# EtherWiz.net
KiCad netlist of a schematic drawn in Altium Designer
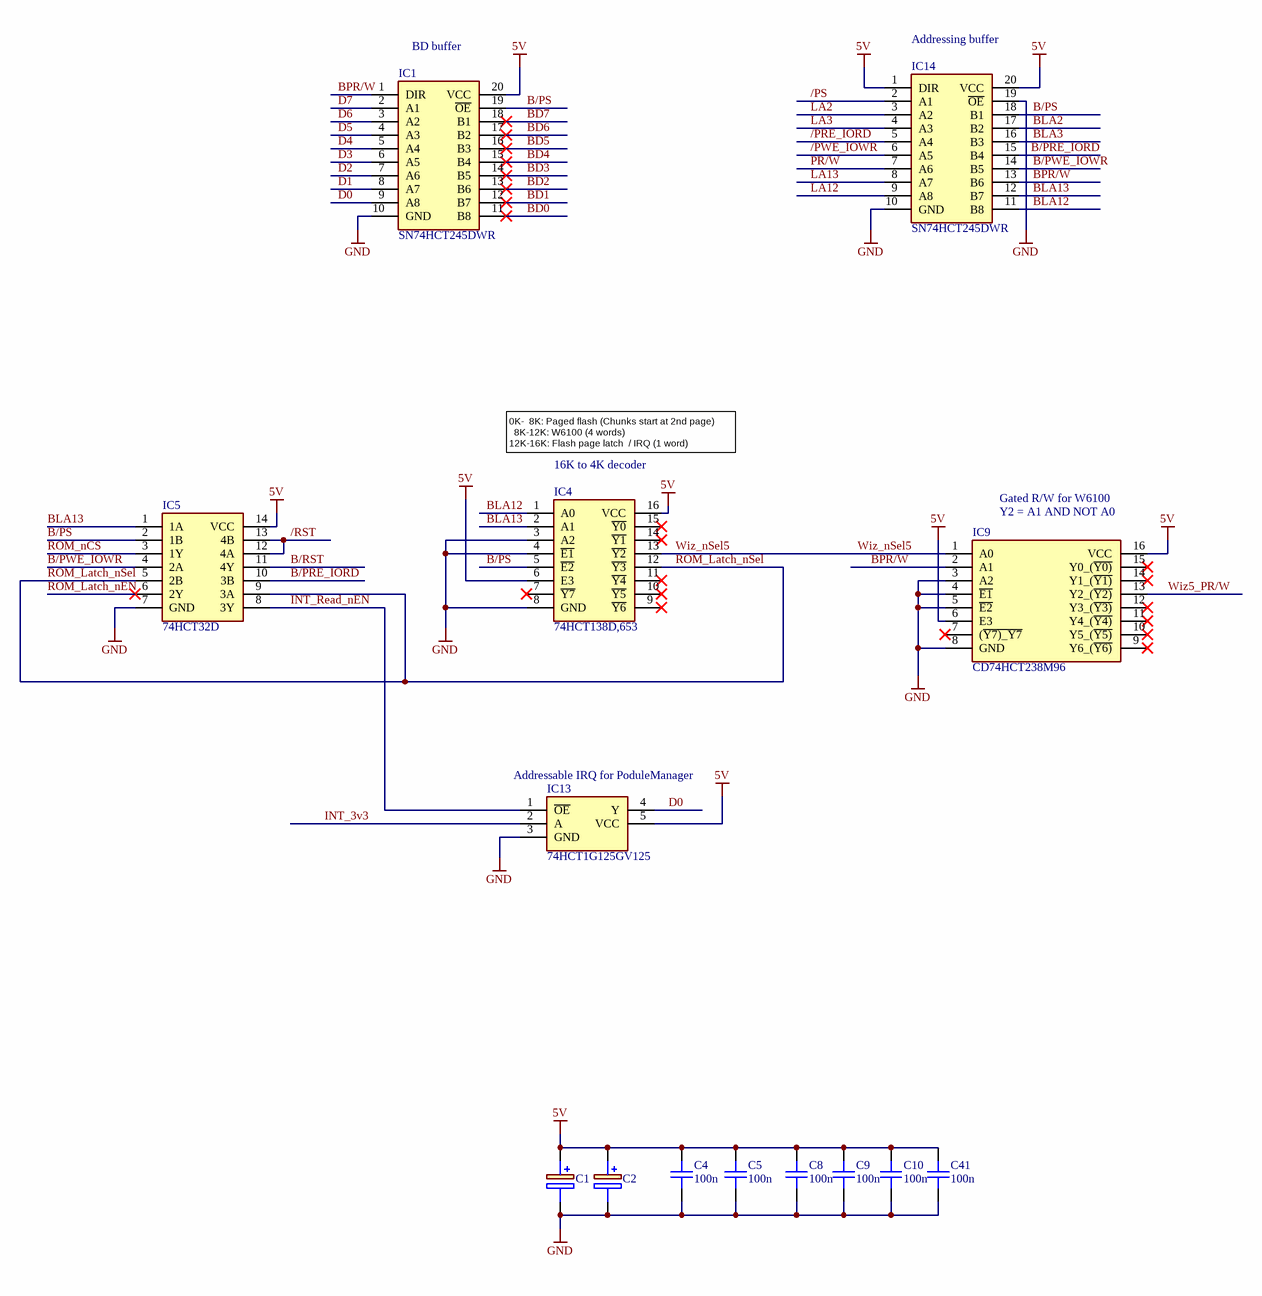
[diagram p0: EtherWiz.SchDoc]

(export (version "E")
  (design (tool "Eeschema 10.0.6"))
  (components
    (comp (ref "C1")
      (value "EEE-HA1C470AP")
      (footprint "SamacSys:EEE1AA101SP")
      (description "Capacitor Polarised")
      (fields (field (name "MOUSER PART NUMBER") "667-EEE-HA1C470AP"))
      (libsource (lib "*") (part "EEE-HA1C470AP"))
    )
    (comp (ref "C2")
      (value "EEE-HA1C470AP")
      (footprint "SamacSys:EEE1AA101SP")
      (description "Capacitor Polarised")
      (fields (field (name "MOUSER PART NUMBER") "667-EEE-HA1C470AP"))
      (libsource (lib "*") (part "EEE-HA1C470AP"))
    )
    (comp (ref "C4")
      (value "100n")
      (footprint "CAPC1608L")
      (description "CAP 100nF, 0603, 50V, X7R, 10%")
      (fields
        (field (name "DISTRIBUTOR1 PART NO") "CL10B104KB8NNNC")
        (field (name "DISTRIBUTOR2 PART NO") "311-1344-2-ND")
      )
      (libsource (lib "MCP1002_RevC") (part "CAP_100n_0603_50V_0"))
    )
    (comp (ref "C5")
      (value "100n")
      (footprint "CAPC1608L")
      (description "CAP 100nF, 0603, 50V, X7R, 10%")
      (fields
        (field (name "DISTRIBUTOR1 PART NO") "CL10B104KB8NNNC")
        (field (name "DISTRIBUTOR2 PART NO") "311-1344-2-ND")
      )
      (libsource (lib "MCP1002_RevC") (part "CAP_100n_0603_50V_0"))
    )
    (comp (ref "C8")
      (value "100n")
      (footprint "CAPC1608L")
      (description "CAP 100nF, 0603, 50V, X7R, 10%")
      (fields
        (field (name "DISTRIBUTOR1 PART NO") "CL10B104KB8NNNC")
        (field (name "DISTRIBUTOR2 PART NO") "311-1344-2-ND")
      )
      (libsource (lib "MCP1002_RevC") (part "CAP_100n_0603_50V_0"))
    )
    (comp (ref "C9")
      (value "100n")
      (footprint "CAPC1608L")
      (description "CAP 100nF, 0603, 50V, X7R, 10%")
      (fields
        (field (name "DISTRIBUTOR1 PART NO") "CL10B104KB8NNNC")
        (field (name "DISTRIBUTOR2 PART NO") "311-1344-2-ND")
      )
      (libsource (lib "MCP1002_RevC") (part "CAP_100n_0603_50V_0"))
    )
    (comp (ref "C10")
      (value "100n")
      (footprint "CAPC1608L")
      (description "CAP 100nF, 0603, 50V, X7R, 10%")
      (fields
        (field (name "DISTRIBUTOR1 PART NO") "CL10B104KB8NNNC")
        (field (name "DISTRIBUTOR2 PART NO") "311-1344-2-ND")
      )
      (libsource (lib "MCP1002_RevC") (part "CAP_100n_0603_50V_0"))
    )
    (comp (ref "C41")
      (value "100n")
      (footprint "CAPC1608L")
      (description "CAP 100nF, 0603, 50V, X7R, 10%")
      (fields
        (field (name "DISTRIBUTOR1 PART NO") "CL10B104KB8NNNC")
        (field (name "DISTRIBUTOR2 PART NO") "311-1344-2-ND")
      )
      (libsource (lib "MCP1002_RevC") (part "CAP_100n_0603_50V_0"))
    )
    (comp (ref "IC1")
      (value "SN74HCT245DWR")
      (footprint "SamacSys:SOIC127P1030X265-20N")
      (description "Integrated Circuit")
      (fields (field (name "MOUSER PART NUMBER") "595-SN74HCT245DWR"))
      (libsource (lib "*") (part "SN74HCT245DWR"))
    )
    (comp (ref "IC4")
      (value "74HCT138D,653")
      (footprint "SamacSys:SOIC127P600X175-16N")
      (description "Integrated Circuit")
      (fields (field (name "MOUSER PART NUMBER") "771-74HCT138D-T"))
      (libsource (lib "*") (part "74HCT138D,653"))
    )
    (comp (ref "IC5")
      (value "74HCT32D")
      (footprint "SamacSys:SOIC127P600X175-14N")
      (description "Integrated Circuit")
      (libsource (lib "*") (part "74HCT32D"))
    )
    (comp (ref "IC9")
      (value "CD74HCT238M96")
      (footprint "SamacSys:SOIC127P600X175-16N")
      (description "Integrated Circuit")
      (fields (field (name "MOUSER PART NUMBER") "595-CD74HCT238M96"))
      (libsource (lib "*") (part "CD74HCT238M96"))
    )
    (comp (ref "IC13")
      (value "74HCT1G125GV125")
      (footprint "SamacSys:SOT95P275X110-5N")
      (description "Integrated Circuit")
      (libsource (lib "*") (part "74HCT1G125GV125"))
    )
    (comp (ref "IC14")
      (value "SN74HCT245DWR")
      (footprint "SamacSys:SOIC127P1030X265-20N")
      (description "Integrated Circuit")
      (fields (field (name "MOUSER PART NUMBER") "595-SN74HCT245DWR"))
      (libsource (lib "*") (part "SN74HCT245DWR"))
    )
  )
  (nets
    (net (code "1") (name "/BD0") (class "Default")
      (node (ref "IC1") (pin "11") (pinfunction "B8_11") (pintype "passive+no_connect"))
    )
    (net (code "2") (name "/BD1") (class "Default")
      (node (ref "IC1") (pin "12") (pinfunction "B7_12") (pintype "power_in+no_connect"))
    )
    (net (code "3") (name "/BD2") (class "Default")
      (node (ref "IC1") (pin "13") (pinfunction "B6_13") (pintype "passive+no_connect"))
    )
    (net (code "4") (name "/BD3") (class "Default")
      (node (ref "IC1") (pin "14") (pinfunction "B5_14") (pintype "passive+no_connect"))
    )
    (net (code "5") (name "/BD4") (class "Default")
      (node (ref "IC1") (pin "15") (pinfunction "B4_15") (pintype "passive+no_connect"))
    )
    (net (code "6") (name "/BD5") (class "Default")
      (node (ref "IC1") (pin "16") (pinfunction "B3_16") (pintype "passive+no_connect"))
    )
    (net (code "7") (name "/BD6") (class "Default")
      (node (ref "IC1") (pin "17") (pinfunction "B2_17") (pintype "passive+no_connect"))
    )
    (net (code "8") (name "/BD7") (class "Default")
      (node (ref "IC1") (pin "18") (pinfunction "B1_18") (pintype "passive+no_connect"))
    )
    (net (code "9") (name "/BLA2") (class "Default")
      (node (ref "IC14") (pin "17") (pinfunction "B2_17") (pintype "passive"))
    )
    (net (code "10") (name "/BLA3") (class "Default")
      (node (ref "IC14") (pin "16") (pinfunction "B3_16") (pintype "passive"))
    )
    (net (code "11") (name "/BLA12") (class "Default")
      (node (ref "IC14") (pin "11") (pinfunction "B8_11") (pintype "passive"))
      (node (ref "IC4") (pin "1") (pinfunction "A0_1") (pintype "passive"))
    )
    (net (code "12") (name "/BLA13") (class "Default")
      (node (ref "IC14") (pin "12") (pinfunction "B7_12") (pintype "power_in"))
      (node (ref "IC4") (pin "2") (pinfunction "A1_2") (pintype "passive"))
      (node (ref "IC5") (pin "1") (pinfunction "1A_1") (pintype "passive"))
    )
    (net (code "13") (name "/BPR{slash}W") (class "Default")
      (node (ref "IC1") (pin "1") (pinfunction "DIR_1") (pintype "passive"))
      (node (ref "IC14") (pin "13") (pinfunction "B6_13") (pintype "passive"))
      (node (ref "IC9") (pin "2") (pinfunction "A1_2") (pintype "passive"))
    )
    (net (code "14") (name "/B{slash}PRE_IORD") (class "Default")
      (node (ref "IC14") (pin "15") (pinfunction "B4_15") (pintype "passive"))
      (node (ref "IC5") (pin "10") (pinfunction "3B_10") (pintype "passive"))
    )
    (net (code "15") (name "/B{slash}PS") (class "Default")
      (node (ref "IC1") (pin "19") (pinfunction "~{OE}_19") (pintype "passive"))
      (node (ref "IC14") (pin "18") (pinfunction "B1_18") (pintype "passive"))
      (node (ref "IC4") (pin "5") (pinfunction "~{E2}_5") (pintype "passive"))
      (node (ref "IC5") (pin "2") (pinfunction "1B_2") (pintype "passive"))
    )
    (net (code "16") (name "/B{slash}PWE_IOWR") (class "Default")
      (node (ref "IC14") (pin "14") (pinfunction "B5_14") (pintype "passive"))
      (node (ref "IC5") (pin "4") (pinfunction "2A_4") (pintype "passive"))
    )
    (net (code "17") (name "/B{slash}RST") (class "Default")
      (node (ref "IC5") (pin "11") (pinfunction "4Y_11") (pintype "passive"))
    )
    (net (code "18") (name "/D0") (class "Default")
      (node (ref "IC1") (pin "9") (pinfunction "A8_9") (pintype "passive"))
      (node (ref "IC13") (pin "4") (pinfunction "Y_4") (pintype "passive"))
    )
    (net (code "19") (name "/D1") (class "Default")
      (node (ref "IC1") (pin "8") (pinfunction "A7_8") (pintype "passive"))
    )
    (net (code "20") (name "/D2") (class "Default")
      (node (ref "IC1") (pin "7") (pinfunction "A6_7") (pintype "passive"))
    )
    (net (code "21") (name "/D3") (class "Default")
      (node (ref "IC1") (pin "6") (pinfunction "A5_6") (pintype "passive"))
    )
    (net (code "22") (name "/D4") (class "Default")
      (node (ref "IC1") (pin "5") (pinfunction "A4_5") (pintype "passive"))
    )
    (net (code "23") (name "/D5") (class "Default")
      (node (ref "IC1") (pin "4") (pinfunction "A3_4") (pintype "passive"))
    )
    (net (code "24") (name "/D6") (class "Default")
      (node (ref "IC1") (pin "3") (pinfunction "A2_3") (pintype "passive"))
    )
    (net (code "25") (name "/D7") (class "Default")
      (node (ref "IC1") (pin "2") (pinfunction "A1_2") (pintype "passive"))
    )
    (net (code "26") (name "/INT_3v3") (class "Default")
      (node (ref "IC13") (pin "2") (pinfunction "A_2") (pintype "passive"))
    )
    (net (code "27") (name "/INT_Read_nEN") (class "Default")
      (node (ref "IC13") (pin "1") (pinfunction "~{OE}_1") (pintype "passive"))
      (node (ref "IC5") (pin "8") (pinfunction "3Y_8") (pintype "passive"))
    )
    (net (code "28") (name "/LA2") (class "Default")
      (node (ref "IC14") (pin "3") (pinfunction "A2_3") (pintype "passive"))
    )
    (net (code "29") (name "/LA3") (class "Default")
      (node (ref "IC14") (pin "4") (pinfunction "A3_4") (pintype "passive"))
    )
    (net (code "30") (name "/LA12") (class "Default")
      (node (ref "IC14") (pin "9") (pinfunction "A8_9") (pintype "passive"))
    )
    (net (code "31") (name "/LA13") (class "Default")
      (node (ref "IC14") (pin "8") (pinfunction "A7_8") (pintype "passive"))
    )
    (net (code "32") (name "/PR{slash}W") (class "Default")
      (node (ref "IC14") (pin "7") (pinfunction "A6_7") (pintype "passive"))
    )
    (net (code "33") (name "/ROM_Latch_nEN") (class "Default")
      (node (ref "IC5") (pin "6") (pinfunction "2Y_6") (pintype "passive+no_connect"))
    )
    (net (code "34") (name "/ROM_Latch_nSel") (class "Default")
      (node (ref "IC4") (pin "12") (pinfunction "~{Y3}_12") (pintype "passive"))
      (node (ref "IC5") (pin "5") (pinfunction "2B_5") (pintype "passive"))
      (node (ref "IC5") (pin "9") (pinfunction "3A_9") (pintype "passive"))
    )
    (net (code "35") (name "/ROM_nCS") (class "Default")
      (node (ref "IC5") (pin "3") (pinfunction "1Y_3") (pintype "passive"))
    )
    (net (code "36") (name "/Wiz5_PR{slash}W") (class "Default")
      (node (ref "IC9") (pin "13") (pinfunction "Y2_(~{Y2)}_13") (pintype "passive"))
    )
    (net (code "37") (name "/Wiz_nSel5") (class "Default")
      (node (ref "IC4") (pin "13") (pinfunction "~{Y2}_13") (pintype "passive"))
      (node (ref "IC9") (pin "1") (pinfunction "A0_1") (pintype "passive"))
    )
    (net (code "38") (name "/{slash}PRE_IORD") (class "Default")
      (node (ref "IC14") (pin "5") (pinfunction "A4_5") (pintype "passive"))
    )
    (net (code "39") (name "/{slash}PS") (class "Default")
      (node (ref "IC14") (pin "2") (pinfunction "A1_2") (pintype "passive"))
    )
    (net (code "40") (name "/{slash}PWE_IOWR") (class "Default")
      (node (ref "IC14") (pin "6") (pinfunction "A5_6") (pintype "passive"))
    )
    (net (code "41") (name "/{slash}RST") (class "Default")
      (node (ref "IC5") (pin "12") (pinfunction "4A_12") (pintype "passive"))
      (node (ref "IC5") (pin "13") (pinfunction "4B_13") (pintype "passive"))
    )
    (net (code "42") (name "5V") (class "Default")
      (node (ref "C1") (pin "1") (pinfunction "+_1") (pintype "passive"))
      (node (ref "C10") (pin "2") (pintype "passive"))
      (node (ref "C2") (pin "1") (pinfunction "+_1") (pintype "passive"))
      (node (ref "C4") (pin "2") (pintype "passive"))
      (node (ref "C41") (pin "2") (pintype "passive"))
      (node (ref "C5") (pin "2") (pintype "passive"))
      (node (ref "C8") (pin "2") (pintype "passive"))
      (node (ref "C9") (pin "2") (pintype "passive"))
      (node (ref "IC1") (pin "20") (pinfunction "VCC_20") (pintype "power_in"))
      (node (ref "IC13") (pin "5") (pinfunction "VCC_5") (pintype "passive"))
      (node (ref "IC14") (pin "1") (pinfunction "DIR_1") (pintype "passive"))
      (node (ref "IC14") (pin "20") (pinfunction "VCC_20") (pintype "power_in"))
      (node (ref "IC4") (pin "16") (pinfunction "VCC_16") (pintype "passive"))
      (node (ref "IC4") (pin "6") (pinfunction "E3_6") (pintype "passive"))
      (node (ref "IC5") (pin "14") (pinfunction "VCC_14") (pintype "passive"))
      (node (ref "IC9") (pin "16") (pinfunction "VCC_16") (pintype "passive"))
      (node (ref "IC9") (pin "6") (pinfunction "E3_6") (pintype "passive"))
    )
    (net (code "43") (name "GND") (class "Default")
      (node (ref "C1") (pin "2") (pinfunction "-_2") (pintype "passive"))
      (node (ref "C10") (pin "1") (pintype "passive"))
      (node (ref "C2") (pin "2") (pinfunction "-_2") (pintype "passive"))
      (node (ref "C4") (pin "1") (pintype "passive"))
      (node (ref "C41") (pin "1") (pintype "passive"))
      (node (ref "C5") (pin "1") (pintype "passive"))
      (node (ref "C8") (pin "1") (pintype "passive"))
      (node (ref "C9") (pin "1") (pintype "passive"))
      (node (ref "IC1") (pin "10") (pinfunction "GND_10") (pintype "power_in"))
      (node (ref "IC13") (pin "3") (pinfunction "GND_3") (pintype "passive"))
      (node (ref "IC14") (pin "10") (pinfunction "GND_10") (pintype "power_in"))
      (node (ref "IC14") (pin "19") (pinfunction "~{OE}_19") (pintype "passive"))
      (node (ref "IC4") (pin "3") (pinfunction "A2_3") (pintype "passive"))
      (node (ref "IC4") (pin "4") (pinfunction "~{E1}_4") (pintype "passive"))
      (node (ref "IC4") (pin "8") (pinfunction "GND_8") (pintype "passive"))
      (node (ref "IC5") (pin "7") (pinfunction "GND_7") (pintype "passive"))
      (node (ref "IC9") (pin "3") (pinfunction "A2_3") (pintype "passive"))
      (node (ref "IC9") (pin "4") (pinfunction "~{E1}_4") (pintype "passive"))
      (node (ref "IC9") (pin "5") (pinfunction "~{E2}_5") (pintype "passive"))
      (node (ref "IC9") (pin "8") (pinfunction "GND_8") (pintype "passive"))
    )
    (net (code "44") (name "unconnected-(IC4-~{Y0}-Pad15)") (class "Default")
      (node (ref "IC4") (pin "15") (pinfunction "~{Y0}_15") (pintype "passive+no_connect"))
    )
    (net (code "45") (name "unconnected-(IC4-~{Y1}-Pad14)") (class "Default")
      (node (ref "IC4") (pin "14") (pinfunction "~{Y1}_14") (pintype "passive+no_connect"))
    )
    (net (code "46") (name "unconnected-(IC4-~{Y4}-Pad11)") (class "Default")
      (node (ref "IC4") (pin "11") (pinfunction "~{Y4}_11") (pintype "passive+no_connect"))
    )
    (net (code "47") (name "unconnected-(IC4-~{Y5}-Pad10)") (class "Default")
      (node (ref "IC4") (pin "10") (pinfunction "~{Y5}_10") (pintype "passive+no_connect"))
    )
    (net (code "48") (name "unconnected-(IC4-~{Y6}-Pad9)") (class "Default")
      (node (ref "IC4") (pin "9") (pinfunction "~{Y6}_9") (pintype "passive+no_connect"))
    )
    (net (code "49") (name "unconnected-(IC4-~{Y7}-Pad7)") (class "Default")
      (node (ref "IC4") (pin "7") (pinfunction "~{Y7}_7") (pintype "passive+no_connect"))
    )
    (net (code "50") (name "unconnected-(IC9-(~{Y7)_Y7}-Pad7)") (class "Default")
      (node (ref "IC9") (pin "7") (pinfunction "(~{Y7)_Y7}_7") (pintype "passive+no_connect"))
    )
    (net (code "51") (name "unconnected-(IC9-Y0_(~{Y0)}-Pad15)") (class "Default")
      (node (ref "IC9") (pin "15") (pinfunction "Y0_(~{Y0)}_15") (pintype "passive+no_connect"))
    )
    (net (code "52") (name "unconnected-(IC9-Y1_(~{Y1)}-Pad14)") (class "Default")
      (node (ref "IC9") (pin "14") (pinfunction "Y1_(~{Y1)}_14") (pintype "passive+no_connect"))
    )
    (net (code "53") (name "unconnected-(IC9-Y3_(~{Y3)}-Pad12)") (class "Default")
      (node (ref "IC9") (pin "12") (pinfunction "Y3_(~{Y3)}_12") (pintype "passive+no_connect"))
    )
    (net (code "54") (name "unconnected-(IC9-Y4_(~{Y4)}-Pad11)") (class "Default")
      (node (ref "IC9") (pin "11") (pinfunction "Y4_(~{Y4)}_11") (pintype "passive+no_connect"))
    )
    (net (code "55") (name "unconnected-(IC9-Y5_(~{Y5)}-Pad10)") (class "Default")
      (node (ref "IC9") (pin "10") (pinfunction "Y5_(~{Y5)}_10") (pintype "passive+no_connect"))
    )
    (net (code "56") (name "unconnected-(IC9-Y6_(~{Y6)}-Pad9)") (class "Default")
      (node (ref "IC9") (pin "9") (pinfunction "Y6_(~{Y6)}_9") (pintype "passive+no_connect"))
    )
  )
)
